# Controller.net
KiCad netlist of a schematic drawn in Altium Designer
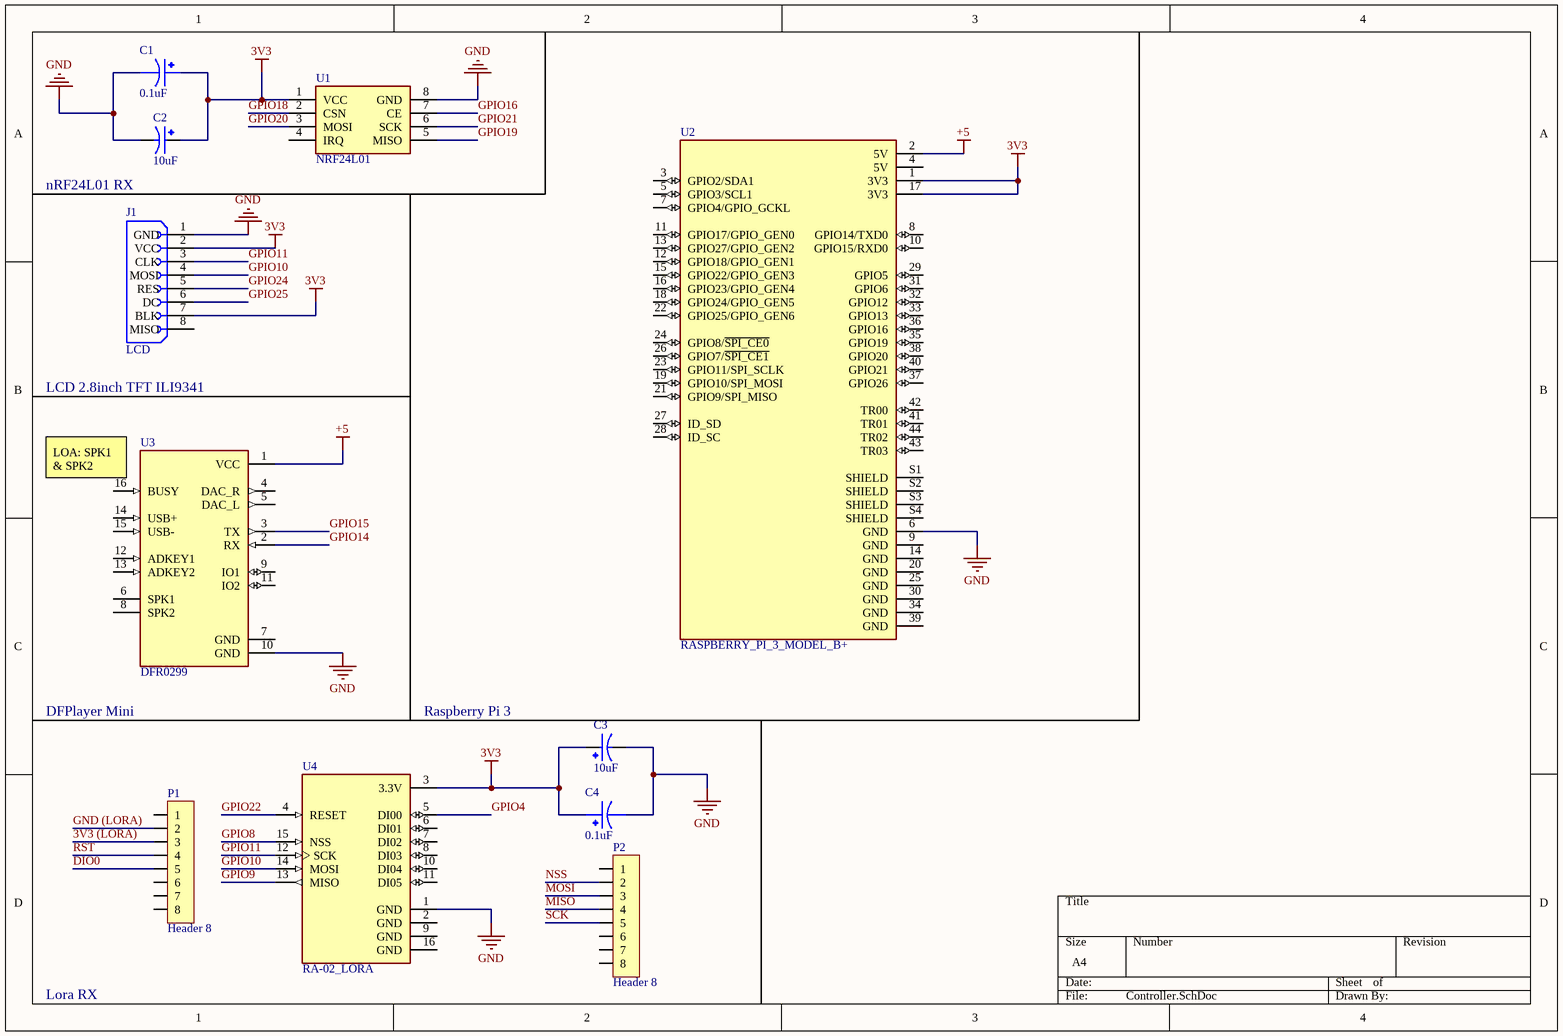
[diagram p0: Controller.SchDoc]

(export (version "E")
  (design (tool "Eeschema 10.0.6"))
  (components
    (comp (ref "C1")
      (value "0.1uF")
      (footprint "CAPPRD200W50D550H1250")
      (description "0.1 ÂµF 100 V Aluminum Electrolytic Capacitors Radial, Can - 2000 Hrs @ 85Â°C")
      (fields (field (name "MF") "Nichicon") (field (name "MP") "UVR2A0R1MDD"))
      (libsource (lib "") (part "UVR2A0R1MDD_1"))
    )
    (comp (ref "C2")
      (value "10uF")
      (footprint "CAPPRD500W50D500H1100")
      (description "10ÂµF 63V Aluminum Electrolytic Capacitors Radial, Can 2000 Hrs @ 85Â°C")
      (fields (field (name "MF") "Panasonic") (field (name "MP") "ECA1JM100B"))
      (libsource (lib "ECA1JM100B") (part "ECA1JM100B"))
    )
    (comp (ref "C3")
      (value "10uF")
      (footprint "CAPPRD500W50D500H1100")
      (description "10ÂµF 63V Aluminum Electrolytic Capacitors Radial, Can 2000 Hrs @ 85Â°C")
      (fields (field (name "MF") "Panasonic") (field (name "MP") "ECA1JM100B"))
      (libsource (lib "") (part "ECA1JM100B_1"))
    )
    (comp (ref "C4")
      (value "0.1uF")
      (footprint "CAPPRD200W50D550H1250")
      (description "0.1 ÂµF 100 V Aluminum Electrolytic Capacitors Radial, Can - 2000 Hrs @ 85Â°C")
      (fields (field (name "MF") "Nichicon") (field (name "MP") "UVR2A0R1MDD"))
      (libsource (lib "UVR2A0R1MDD") (part "UVR2A0R1MDD"))
    )
    (comp (ref "J1")
      (value "LCD")
      (footprint "GRAVITECH_8FX1-254MM")
      (description "Headers & Wire Housings 2.54MM 0.1 8-PIN FEMALE HEADER")
      (fields (field (name "MP") "8Fx1-254mm") (field (name "MF") "Gravitech"))
      (libsource (lib "8FX1-254MM") (part "8FX1-254MM"))
    )
    (comp (ref "P1")
      (value "Header 8")
      (footprint "HDR/Header/8")
      (description "Header, 8-Pin")
      (libsource (lib "connectors") (part "Header 8"))
    )
    (comp (ref "P2")
      (value "Header 8")
      (footprint "HDR/Header/8")
      (description "Header, 8-Pin")
      (libsource (lib "connectors") (part "Header 8"))
    )
    (comp (ref "U1")
      (value "NRF24L01")
      (footprint "NRF24L01")
      (description "MÓDULO TRANSCEPTOR RF WIRELESS 2.4GHZ")
      (libsource (lib "Communication") (part "NRF24L01"))
    )
    (comp (ref "U2")
      (value "RASPBERRY_PI_3_MODEL_B+")
      (footprint "MODULE_RASPBERRY_PI_3_MODEL_B+")
      (fields (field (name "MF") "Raspberry Pi") (field (name "MP") "RASPBERRY PI 3 MODEL B+"))
      (libsource (lib "RASPBERRY_PI_3_MODEL_B_") (part "RASPBERRY_PI_3_MODEL_B+"))
    )
    (comp (ref "U3")
      (value "DFR0299")
      (footprint "MODULE_DFR0299")
      (description "- MP3 Player Audio Arduino Platform Evaluation Expansion Board")
      (fields (field (name "MF") "DFRobot"))
      (libsource (lib "DFR0299") (part "DFR0299"))
    )
    (comp (ref "U4")
      (value "RA-02_LORA")
      (footprint "MODULE_RA-02_LORA")
      (description "Ra-02 LoRa RF M5Stack Platform Evaluation Expansion Board")
      (libsource (lib "RA-02_LORA") (part "RA-02_LORA"))
    )
  )
  (nets
    (net (code "1") (name "+5") (class "Default")
      (node (ref "U2") (pin "2") (pinfunction "5V_2") (pintype "power_in"))
      (node (ref "U3") (pin "1") (pinfunction "VCC_1") (pintype "power_in"))
    )
    (net (code "2") (name "/3V3 (LORA)") (class "Default")
      (node (ref "P1") (pin "3") (pinfunction "3_3") (pintype "passive"))
    )
    (net (code "3") (name "/DIO0") (class "Default")
      (node (ref "P1") (pin "5") (pinfunction "5_5") (pintype "passive"))
    )
    (net (code "4") (name "/GND (LORA)") (class "Default")
      (node (ref "P1") (pin "2") (pinfunction "2_2") (pintype "passive"))
    )
    (net (code "5") (name "/GPIO4") (class "Default")
      (node (ref "U4") (pin "5") (pinfunction "DI00_5") (pintype "bidirectional"))
    )
    (net (code "6") (name "/GPIO8") (class "Default")
      (node (ref "U4") (pin "15") (pinfunction "NSS_15") (pintype "input"))
    )
    (net (code "7") (name "/GPIO9") (class "Default")
      (node (ref "U4") (pin "13") (pinfunction "MISO_13") (pintype "output"))
    )
    (net (code "8") (name "/GPIO10") (class "Default")
      (node (ref "J1") (pin "4") (pinfunction "MOSI_4") (pintype "passive"))
      (node (ref "U4") (pin "14") (pinfunction "MOSI_14") (pintype "input"))
    )
    (net (code "9") (name "/GPIO11") (class "Default")
      (node (ref "J1") (pin "3") (pinfunction "CLK_3") (pintype "passive"))
      (node (ref "U4") (pin "12") (pinfunction "SCK_12") (pintype "input"))
    )
    (net (code "10") (name "/GPIO14") (class "Default")
      (node (ref "U3") (pin "2") (pinfunction "RX_2") (pintype "input"))
    )
    (net (code "11") (name "/GPIO15") (class "Default")
      (node (ref "U3") (pin "3") (pinfunction "TX_3") (pintype "output"))
    )
    (net (code "12") (name "/GPIO16") (class "Default")
      (node (ref "U1") (pin "7") (pinfunction "CE_7") (pintype "passive"))
    )
    (net (code "13") (name "/GPIO18") (class "Default")
      (node (ref "U1") (pin "2") (pinfunction "CSN_2") (pintype "passive"))
    )
    (net (code "14") (name "/GPIO19") (class "Default")
      (node (ref "U1") (pin "5") (pinfunction "MISO_5") (pintype "passive"))
    )
    (net (code "15") (name "/GPIO20") (class "Default")
      (node (ref "U1") (pin "3") (pinfunction "MOSI_3") (pintype "passive"))
    )
    (net (code "16") (name "/GPIO21") (class "Default")
      (node (ref "U1") (pin "6") (pinfunction "SCK_6") (pintype "passive"))
    )
    (net (code "17") (name "/GPIO22") (class "Default")
      (node (ref "U4") (pin "4") (pinfunction "RESET_4") (pintype "input"))
    )
    (net (code "18") (name "/GPIO24") (class "Default")
      (node (ref "J1") (pin "5") (pinfunction "RES_5") (pintype "passive"))
    )
    (net (code "19") (name "/GPIO25") (class "Default")
      (node (ref "J1") (pin "6") (pinfunction "DC_6") (pintype "passive"))
    )
    (net (code "20") (name "/MISO") (class "Default")
      (node (ref "P2") (pin "4") (pinfunction "4_4") (pintype "passive"))
    )
    (net (code "21") (name "/MOSI") (class "Default")
      (node (ref "P2") (pin "3") (pinfunction "3_3") (pintype "passive"))
    )
    (net (code "22") (name "/NSS") (class "Default")
      (node (ref "P2") (pin "2") (pinfunction "2_2") (pintype "passive"))
    )
    (net (code "23") (name "/RST") (class "Default")
      (node (ref "P1") (pin "4") (pinfunction "4_4") (pintype "passive"))
    )
    (net (code "24") (name "/SCK") (class "Default")
      (node (ref "P2") (pin "5") (pinfunction "5_5") (pintype "passive"))
    )
    (net (code "25") (name "3V3") (class "Default")
      (node (ref "C1") (pin "1") (pinfunction "1_1") (pintype "passive"))
      (node (ref "C2") (pin "P") (pinfunction "P_P") (pintype "passive"))
      (node (ref "C3") (pin "P") (pinfunction "P_P") (pintype "passive"))
      (node (ref "C4") (pin "1") (pinfunction "1_1") (pintype "passive"))
      (node (ref "J1") (pin "2") (pinfunction "VCC_2") (pintype "passive"))
      (node (ref "J1") (pin "7") (pinfunction "BLK_7") (pintype "passive"))
      (node (ref "U1") (pin "1") (pinfunction "VCC_1") (pintype "passive"))
      (node (ref "U2") (pin "1") (pinfunction "3V3_1") (pintype "power_in"))
      (node (ref "U2") (pin "17") (pinfunction "3V3_17") (pintype "power_in"))
      (node (ref "U4") (pin "3") (pinfunction "3.3V_3") (pintype "power_in"))
    )
    (net (code "26") (name "GND") (class "Default")
      (node (ref "C1") (pin "2") (pinfunction "2_2") (pintype "passive"))
      (node (ref "C2") (pin "N") (pinfunction "N_N") (pintype "passive"))
      (node (ref "C3") (pin "N") (pinfunction "N_N") (pintype "passive"))
      (node (ref "C4") (pin "2") (pinfunction "2_2") (pintype "passive"))
      (node (ref "J1") (pin "1") (pinfunction "GND_1") (pintype "passive"))
      (node (ref "U1") (pin "8") (pinfunction "GND_8") (pintype "passive"))
      (node (ref "U2") (pin "6") (pinfunction "GND_6") (pintype "power_in"))
      (node (ref "U3") (pin "10") (pinfunction "GND_10") (pintype "power_in"))
      (node (ref "U4") (pin "1") (pinfunction "GND_1") (pintype "power_in"))
    )
    (net (code "27") (name "unconnected-(J1-MISO-Pad8)") (class "Default")
      (node (ref "J1") (pin "8") (pinfunction "MISO_8") (pintype "passive"))
    )
    (net (code "28") (name "unconnected-(P1-Pad1)") (class "Default")
      (node (ref "P1") (pin "1") (pinfunction "1_1") (pintype "passive"))
    )
    (net (code "29") (name "unconnected-(P1-Pad6)") (class "Default")
      (node (ref "P1") (pin "6") (pinfunction "6_6") (pintype "passive"))
    )
    (net (code "30") (name "unconnected-(P1-Pad7)") (class "Default")
      (node (ref "P1") (pin "7") (pinfunction "7_7") (pintype "passive"))
    )
    (net (code "31") (name "unconnected-(P1-Pad8)") (class "Default")
      (node (ref "P1") (pin "8") (pinfunction "8_8") (pintype "passive"))
    )
    (net (code "32") (name "unconnected-(P2-Pad1)") (class "Default")
      (node (ref "P2") (pin "1") (pinfunction "1_1") (pintype "passive"))
    )
    (net (code "33") (name "unconnected-(P2-Pad6)") (class "Default")
      (node (ref "P2") (pin "6") (pinfunction "6_6") (pintype "passive"))
    )
    (net (code "34") (name "unconnected-(P2-Pad7)") (class "Default")
      (node (ref "P2") (pin "7") (pinfunction "7_7") (pintype "passive"))
    )
    (net (code "35") (name "unconnected-(P2-Pad8)") (class "Default")
      (node (ref "P2") (pin "8") (pinfunction "8_8") (pintype "passive"))
    )
    (net (code "36") (name "unconnected-(U1-IRQ-Pad4)") (class "Default")
      (node (ref "U1") (pin "4") (pinfunction "IRQ_4") (pintype "passive"))
    )
    (net (code "37") (name "unconnected-(U2-5V-Pad4)") (class "Default")
      (node (ref "U2") (pin "4") (pinfunction "5V_4") (pintype "power_in"))
    )
    (net (code "38") (name "unconnected-(U2-GND-Pad9)") (class "Default")
      (node (ref "U2") (pin "9") (pinfunction "GND_9") (pintype "power_in"))
    )
    (net (code "39") (name "unconnected-(U2-GND-Pad14)") (class "Default")
      (node (ref "U2") (pin "14") (pinfunction "GND_14") (pintype "power_in"))
    )
    (net (code "40") (name "unconnected-(U2-GND-Pad20)") (class "Default")
      (node (ref "U2") (pin "20") (pinfunction "GND_20") (pintype "power_in"))
    )
    (net (code "41") (name "unconnected-(U2-GND-Pad25)") (class "Default")
      (node (ref "U2") (pin "25") (pinfunction "GND_25") (pintype "power_in"))
    )
    (net (code "42") (name "unconnected-(U2-GND-Pad30)") (class "Default")
      (node (ref "U2") (pin "30") (pinfunction "GND_30") (pintype "power_in"))
    )
    (net (code "43") (name "unconnected-(U2-GND-Pad34)") (class "Default")
      (node (ref "U2") (pin "34") (pinfunction "GND_34") (pintype "power_in"))
    )
    (net (code "44") (name "unconnected-(U2-GND-Pad39)") (class "Default")
      (node (ref "U2") (pin "39") (pinfunction "GND_39") (pintype "power_in"))
    )
    (net (code "45") (name "unconnected-(U2-GPIO2{slash}SDA1-Pad3)") (class "Default")
      (node (ref "U2") (pin "3") (pinfunction "GPIO2/SDA1_3") (pintype "bidirectional"))
    )
    (net (code "46") (name "unconnected-(U2-GPIO3{slash}SCL1-Pad5)") (class "Default")
      (node (ref "U2") (pin "5") (pinfunction "GPIO3/SCL1_5") (pintype "bidirectional"))
    )
    (net (code "47") (name "unconnected-(U2-GPIO4{slash}GPIO_GCKL-Pad7)") (class "Default")
      (node (ref "U2") (pin "7") (pinfunction "GPIO4/GPIO_GCKL_7") (pintype "bidirectional"))
    )
    (net (code "48") (name "unconnected-(U2-GPIO5-Pad29)") (class "Default")
      (node (ref "U2") (pin "29") (pinfunction "GPIO5_29") (pintype "bidirectional"))
    )
    (net (code "49") (name "unconnected-(U2-GPIO6-Pad31)") (class "Default")
      (node (ref "U2") (pin "31") (pinfunction "GPIO6_31") (pintype "bidirectional"))
    )
    (net (code "50") (name "unconnected-(U2-GPIO7{slash}~{SPI_CE1}-Pad26)") (class "Default")
      (node (ref "U2") (pin "26") (pinfunction "GPIO7/~{SPI_CE1}_26") (pintype "bidirectional"))
    )
    (net (code "51") (name "unconnected-(U2-GPIO8{slash}~{SPI_CE0}-Pad24)") (class "Default")
      (node (ref "U2") (pin "24") (pinfunction "GPIO8/~{SPI_CE0}_24") (pintype "bidirectional"))
    )
    (net (code "52") (name "unconnected-(U2-GPIO9{slash}SPI_MISO-Pad21)") (class "Default")
      (node (ref "U2") (pin "21") (pinfunction "GPIO9/SPI_MISO_21") (pintype "bidirectional"))
    )
    (net (code "53") (name "unconnected-(U2-GPIO10{slash}SPI_MOSI-Pad19)") (class "Default")
      (node (ref "U2") (pin "19") (pinfunction "GPIO10/SPI_MOSI_19") (pintype "bidirectional"))
    )
    (net (code "54") (name "unconnected-(U2-GPIO11{slash}SPI_SCLK-Pad23)") (class "Default")
      (node (ref "U2") (pin "23") (pinfunction "GPIO11/SPI_SCLK_23") (pintype "bidirectional"))
    )
    (net (code "55") (name "unconnected-(U2-GPIO12-Pad32)") (class "Default")
      (node (ref "U2") (pin "32") (pinfunction "GPIO12_32") (pintype "bidirectional"))
    )
    (net (code "56") (name "unconnected-(U2-GPIO13-Pad33)") (class "Default")
      (node (ref "U2") (pin "33") (pinfunction "GPIO13_33") (pintype "bidirectional"))
    )
    (net (code "57") (name "unconnected-(U2-GPIO14{slash}TXD0-Pad8)") (class "Default")
      (node (ref "U2") (pin "8") (pinfunction "GPIO14/TXD0_8") (pintype "bidirectional"))
    )
    (net (code "58") (name "unconnected-(U2-GPIO15{slash}RXD0-Pad10)") (class "Default")
      (node (ref "U2") (pin "10") (pinfunction "GPIO15/RXD0_10") (pintype "bidirectional"))
    )
    (net (code "59") (name "unconnected-(U2-GPIO16-Pad36)") (class "Default")
      (node (ref "U2") (pin "36") (pinfunction "GPIO16_36") (pintype "bidirectional"))
    )
    (net (code "60") (name "unconnected-(U2-GPIO17{slash}GPIO_GEN0-Pad11)") (class "Default")
      (node (ref "U2") (pin "11") (pinfunction "GPIO17/GPIO_GEN0_11") (pintype "bidirectional"))
    )
    (net (code "61") (name "unconnected-(U2-GPIO18{slash}GPIO_GEN1-Pad12)") (class "Default")
      (node (ref "U2") (pin "12") (pinfunction "GPIO18/GPIO_GEN1_12") (pintype "bidirectional"))
    )
    (net (code "62") (name "unconnected-(U2-GPIO19-Pad35)") (class "Default")
      (node (ref "U2") (pin "35") (pinfunction "GPIO19_35") (pintype "bidirectional"))
    )
    (net (code "63") (name "unconnected-(U2-GPIO20-Pad38)") (class "Default")
      (node (ref "U2") (pin "38") (pinfunction "GPIO20_38") (pintype "bidirectional"))
    )
    (net (code "64") (name "unconnected-(U2-GPIO21-Pad40)") (class "Default")
      (node (ref "U2") (pin "40") (pinfunction "GPIO21_40") (pintype "bidirectional"))
    )
    (net (code "65") (name "unconnected-(U2-GPIO22{slash}GPIO_GEN3-Pad15)") (class "Default")
      (node (ref "U2") (pin "15") (pinfunction "GPIO22/GPIO_GEN3_15") (pintype "bidirectional"))
    )
    (net (code "66") (name "unconnected-(U2-GPIO23{slash}GPIO_GEN4-Pad16)") (class "Default")
      (node (ref "U2") (pin "16") (pinfunction "GPIO23/GPIO_GEN4_16") (pintype "bidirectional"))
    )
    (net (code "67") (name "unconnected-(U2-GPIO24{slash}GPIO_GEN5-Pad18)") (class "Default")
      (node (ref "U2") (pin "18") (pinfunction "GPIO24/GPIO_GEN5_18") (pintype "bidirectional"))
    )
    (net (code "68") (name "unconnected-(U2-GPIO25{slash}GPIO_GEN6-Pad22)") (class "Default")
      (node (ref "U2") (pin "22") (pinfunction "GPIO25/GPIO_GEN6_22") (pintype "bidirectional"))
    )
    (net (code "69") (name "unconnected-(U2-GPIO26-Pad37)") (class "Default")
      (node (ref "U2") (pin "37") (pinfunction "GPIO26_37") (pintype "bidirectional"))
    )
    (net (code "70") (name "unconnected-(U2-GPIO27{slash}GPIO_GEN2-Pad13)") (class "Default")
      (node (ref "U2") (pin "13") (pinfunction "GPIO27/GPIO_GEN2_13") (pintype "bidirectional"))
    )
    (net (code "71") (name "unconnected-(U2-ID_SC-Pad28)") (class "Default")
      (node (ref "U2") (pin "28") (pinfunction "ID_SC_28") (pintype "bidirectional"))
    )
    (net (code "72") (name "unconnected-(U2-ID_SD-Pad27)") (class "Default")
      (node (ref "U2") (pin "27") (pinfunction "ID_SD_27") (pintype "bidirectional"))
    )
    (net (code "73") (name "unconnected-(U2-SHIELD-PadS1)") (class "Default")
      (node (ref "U2") (pin "S1") (pinfunction "SHIELD_S1") (pintype "power_in"))
    )
    (net (code "74") (name "unconnected-(U2-SHIELD-PadS2)") (class "Default")
      (node (ref "U2") (pin "S2") (pinfunction "SHIELD_S2") (pintype "power_in"))
    )
    (net (code "75") (name "unconnected-(U2-SHIELD-PadS3)") (class "Default")
      (node (ref "U2") (pin "S3") (pinfunction "SHIELD_S3") (pintype "power_in"))
    )
    (net (code "76") (name "unconnected-(U2-SHIELD-PadS4)") (class "Default")
      (node (ref "U2") (pin "S4") (pinfunction "SHIELD_S4") (pintype "power_in"))
    )
    (net (code "77") (name "unconnected-(U2-TR00-Pad42)") (class "Default")
      (node (ref "U2") (pin "42") (pinfunction "TR00_42") (pintype "bidirectional"))
    )
    (net (code "78") (name "unconnected-(U2-TR01-Pad41)") (class "Default")
      (node (ref "U2") (pin "41") (pinfunction "TR01_41") (pintype "bidirectional"))
    )
    (net (code "79") (name "unconnected-(U2-TR02-Pad44)") (class "Default")
      (node (ref "U2") (pin "44") (pinfunction "TR02_44") (pintype "bidirectional"))
    )
    (net (code "80") (name "unconnected-(U2-TR03-Pad43)") (class "Default")
      (node (ref "U2") (pin "43") (pinfunction "TR03_43") (pintype "bidirectional"))
    )
    (net (code "81") (name "unconnected-(U3-ADKEY1-Pad12)") (class "Default")
      (node (ref "U3") (pin "12") (pinfunction "ADKEY1_12") (pintype "input"))
    )
    (net (code "82") (name "unconnected-(U3-ADKEY2-Pad13)") (class "Default")
      (node (ref "U3") (pin "13") (pinfunction "ADKEY2_13") (pintype "input"))
    )
    (net (code "83") (name "unconnected-(U3-BUSY-Pad16)") (class "Default")
      (node (ref "U3") (pin "16") (pinfunction "BUSY_16") (pintype "input"))
    )
    (net (code "84") (name "unconnected-(U3-DAC_L-Pad5)") (class "Default")
      (node (ref "U3") (pin "5") (pinfunction "DAC_L_5") (pintype "output"))
    )
    (net (code "85") (name "unconnected-(U3-DAC_R-Pad4)") (class "Default")
      (node (ref "U3") (pin "4") (pinfunction "DAC_R_4") (pintype "output"))
    )
    (net (code "86") (name "unconnected-(U3-GND-Pad7)") (class "Default")
      (node (ref "U3") (pin "7") (pinfunction "GND_7") (pintype "power_in"))
    )
    (net (code "87") (name "unconnected-(U3-IO1-Pad9)") (class "Default")
      (node (ref "U3") (pin "9") (pinfunction "IO1_9") (pintype "bidirectional"))
    )
    (net (code "88") (name "unconnected-(U3-IO2-Pad11)") (class "Default")
      (node (ref "U3") (pin "11") (pinfunction "IO2_11") (pintype "bidirectional"))
    )
    (net (code "89") (name "unconnected-(U3-SPK1-Pad6)") (class "Default")
      (node (ref "U3") (pin "6") (pinfunction "SPK1_6") (pintype "passive"))
    )
    (net (code "90") (name "unconnected-(U3-SPK2-Pad8)") (class "Default")
      (node (ref "U3") (pin "8") (pinfunction "SPK2_8") (pintype "passive"))
    )
    (net (code "91") (name "unconnected-(U3-USB+-Pad14)") (class "Default")
      (node (ref "U3") (pin "14") (pinfunction "USB+_14") (pintype "input"))
    )
    (net (code "92") (name "unconnected-(U3-USB--Pad15)") (class "Default")
      (node (ref "U3") (pin "15") (pinfunction "USB-_15") (pintype "input"))
    )
    (net (code "93") (name "unconnected-(U4-DI01-Pad6)") (class "Default")
      (node (ref "U4") (pin "6") (pinfunction "DI01_6") (pintype "bidirectional"))
    )
    (net (code "94") (name "unconnected-(U4-DI02-Pad7)") (class "Default")
      (node (ref "U4") (pin "7") (pinfunction "DI02_7") (pintype "bidirectional"))
    )
    (net (code "95") (name "unconnected-(U4-DI03-Pad8)") (class "Default")
      (node (ref "U4") (pin "8") (pinfunction "DI03_8") (pintype "bidirectional"))
    )
    (net (code "96") (name "unconnected-(U4-DI04-Pad10)") (class "Default")
      (node (ref "U4") (pin "10") (pinfunction "DI04_10") (pintype "bidirectional"))
    )
    (net (code "97") (name "unconnected-(U4-DI05-Pad11)") (class "Default")
      (node (ref "U4") (pin "11") (pinfunction "DI05_11") (pintype "bidirectional"))
    )
    (net (code "98") (name "unconnected-(U4-GND-Pad2)") (class "Default")
      (node (ref "U4") (pin "2") (pinfunction "GND_2") (pintype "power_in"))
    )
    (net (code "99") (name "unconnected-(U4-GND-Pad9)") (class "Default")
      (node (ref "U4") (pin "9") (pinfunction "GND_9") (pintype "power_in"))
    )
    (net (code "100") (name "unconnected-(U4-GND-Pad16)") (class "Default")
      (node (ref "U4") (pin "16") (pinfunction "GND_16") (pintype "power_in"))
    )
  )
)
